# Sheet1.net
KiCad netlist of a schematic drawn in Altium Designer
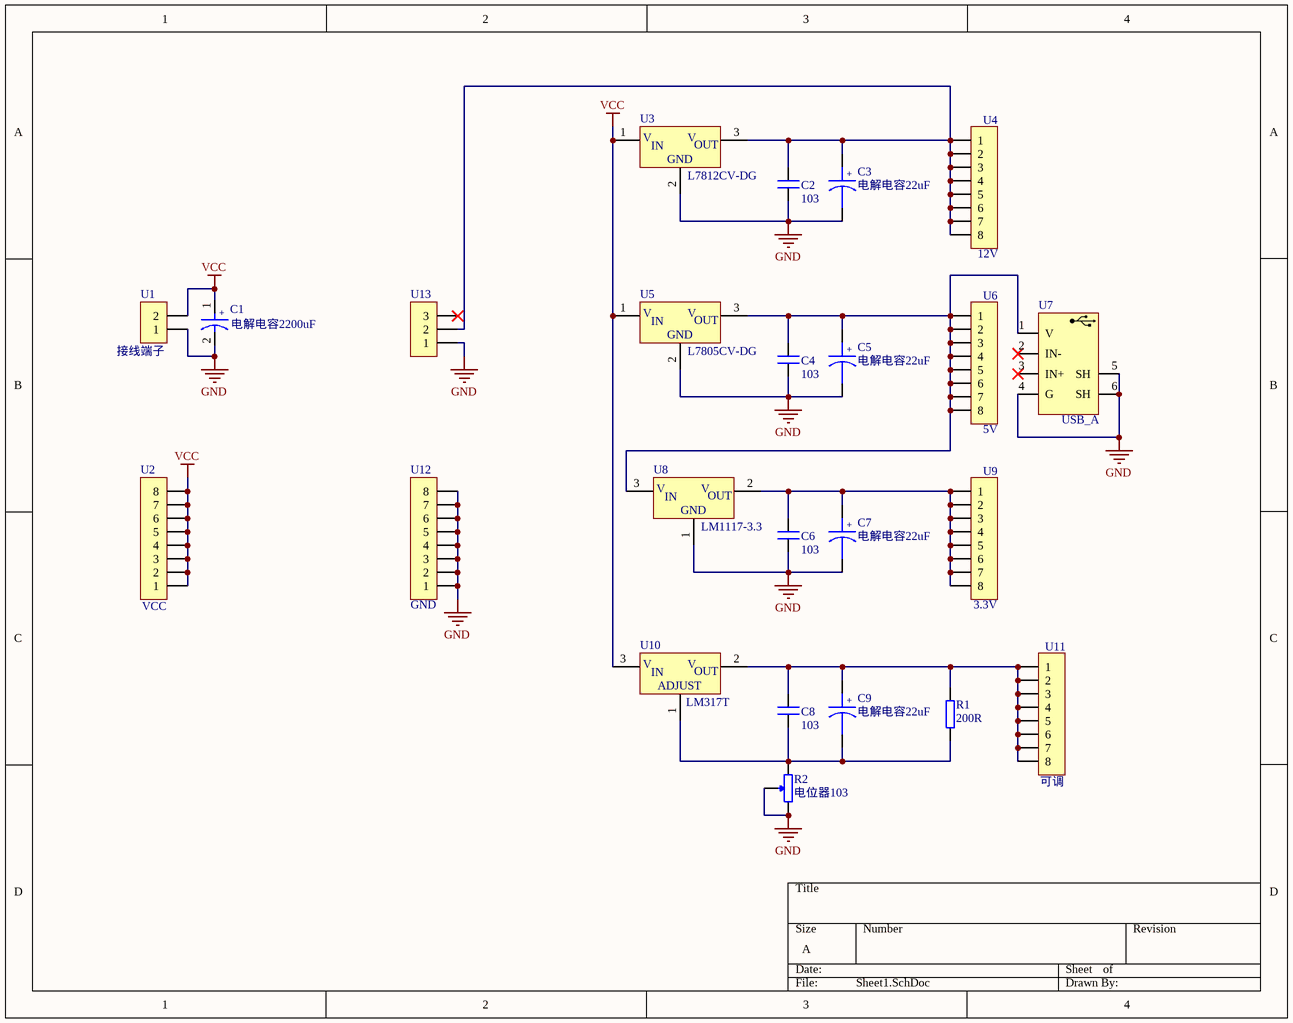
[diagram p0: Sheet1.SchDoc]

(export (version "E")
  (design (tool "Eeschema 10.0.6"))
  (components
    (comp (ref "C1")
      (value "电解电容2200uF")
      (footprint "直插电解电容13*21")
      (libsource (lib "Schlib1") (part "电解电容2200uF"))
    )
    (comp (ref "C2")
      (value "103")
      (footprint "贴片电容1206")
      (description "电容")
      (fields (field (name "版权归属") "源创客"))
      (libsource (lib "Schlib1") (part "Capacitor"))
    )
    (comp (ref "C3")
      (value "电解电容22uF")
      (footprint "直插电解电容5*11")
      (libsource (lib "Schlib1") (part "电解电容22uF"))
    )
    (comp (ref "C4")
      (value "103")
      (footprint "贴片电容1206")
      (description "电容")
      (fields (field (name "版权归属") "源创客"))
      (libsource (lib "Schlib1") (part "Capacitor"))
    )
    (comp (ref "C5")
      (value "电解电容22uF")
      (footprint "直插电解电容5*11")
      (libsource (lib "Schlib1") (part "电解电容22uF"))
    )
    (comp (ref "C6")
      (value "103")
      (footprint "贴片电容1206")
      (description "电容")
      (fields (field (name "版权归属") "源创客"))
      (libsource (lib "Schlib1") (part "Capacitor"))
    )
    (comp (ref "C7")
      (value "电解电容22uF")
      (footprint "直插电解电容5*11")
      (libsource (lib "Schlib1") (part "电解电容22uF"))
    )
    (comp (ref "C8")
      (value "103")
      (footprint "贴片电容1206")
      (description "电容")
      (fields (field (name "版权归属") "源创客"))
      (libsource (lib "Schlib1") (part "Capacitor"))
    )
    (comp (ref "C9")
      (value "电解电容22uF")
      (footprint "直插电解电容5*11")
      (libsource (lib "Schlib1") (part "电解电容22uF"))
    )
    (comp (ref "R1")
      (value "200R")
      (footprint "贴片电阻1206")
      (description "电阻")
      (fields (field (name "版权归属") "源创客"))
      (libsource (lib "Schlib1") (part "Resistor"))
    )
    (comp (ref "R2")
      (value "电位器103")
      (footprint "电位器")
      (description "103")
      (fields (field (name "版权归属") "源创客"))
      (libsource (lib "Schlib1") (part "电位器"))
    )
    (comp (ref "U1")
      (value "接线端子")
      (footprint "KF128-3.81-2P")
      (description "2P接插件")
      (fields (field (name "版权归属") "源创客"))
      (libsource (lib "Schlib1") (part "Header 2"))
    )
    (comp (ref "U2")
      (value "VCC")
      (footprint "HDR-1X8")
      (description "8P接插件")
      (fields (field (name "版权归属") "源创客"))
      (libsource (lib "") (part "Header 8_1"))
    )
    (comp (ref "U3")
      (value "L7812CV-DG")
      (footprint "TO-220")
      (description "3-Terminal Positive Voltage Regulator")
      (libsource (lib "Schlib1") (part "L7812CV-DG"))
    )
    (comp (ref "U4")
      (value "12V")
      (footprint "HDR-1X8")
      (description "8P接插件")
      (fields (field (name "版权归属") "源创客"))
      (libsource (lib "Schlib1") (part "Header 8"))
    )
    (comp (ref "U5")
      (value "L7805CV-DG")
      (footprint "TO-220")
      (description "3-Terminal Positive Voltage Regulator")
      (libsource (lib "Schlib1") (part "L7805CV-DG"))
    )
    (comp (ref "U6")
      (value "5V")
      (footprint "HDR-1X8")
      (description "8P接插件")
      (fields (field (name "版权归属") "源创客"))
      (libsource (lib "Schlib1") (part "Header 8"))
    )
    (comp (ref "U7") (value "USB_A") (footprint "USB-A直插") (libsource (lib "Schlib1") (part "USB_A")))
    (comp (ref "U8")
      (value "LM1117-3.3")
      (footprint "TO-220")
      (description "3-Terminal Positive Voltage Regulator")
      (libsource (lib "Schlib1") (part "LM1117-3.3"))
    )
    (comp (ref "U9")
      (value "3.3V")
      (footprint "HDR-1X8")
      (description "8P接插件")
      (fields (field (name "版权归属") "源创客"))
      (libsource (lib "Schlib1") (part "Header 8"))
    )
    (comp (ref "U10")
      (value "LM317T")
      (footprint "TO-220")
      (description "3-Terminal Positive Voltage Regulator")
      (libsource (lib "Schlib1") (part "LM317T"))
    )
    (comp (ref "U11")
      (value "可调")
      (footprint "HDR-1X8")
      (description "8P接插件")
      (fields (field (name "版权归属") "源创客"))
      (libsource (lib "Schlib1") (part "Header 8"))
    )
    (comp (ref "U12")
      (value "GND")
      (footprint "HDR-1X8")
      (description "8P接插件")
      (fields (field (name "版权归属") "源创客"))
      (libsource (lib "") (part "Header 8_1"))
    )
    (comp (ref "U13")
      (value "接插件")
      (footprint "KF2510")
      (description "3P接插件")
      (fields (field (name "版权归属") "源创客"))
      (libsource (lib "Schlib1") (part "Header 3"))
    )
  )
  (nets
    (net (code "1") (name "GND") (class "Default")
      (node (ref "C1") (pin "2") (pinfunction "2_2") (pintype "passive"))
      (node (ref "C2") (pin "1") (pinfunction "1_1") (pintype "passive"))
      (node (ref "C3") (pin "2") (pinfunction "2_2") (pintype "passive"))
      (node (ref "C4") (pin "1") (pinfunction "1_1") (pintype "passive"))
      (node (ref "C5") (pin "2") (pinfunction "2_2") (pintype "passive"))
      (node (ref "C6") (pin "1") (pinfunction "1_1") (pintype "passive"))
      (node (ref "C7") (pin "2") (pinfunction "2_2") (pintype "passive"))
      (node (ref "R2") (pin "1") (pinfunction "1_1") (pintype "passive"))
      (node (ref "R2") (pin "2") (pinfunction "2_2") (pintype "passive"))
      (node (ref "U1") (pin "1") (pinfunction "1_1") (pintype "passive"))
      (node (ref "U12") (pin "1") (pinfunction "1_1") (pintype "passive"))
      (node (ref "U12") (pin "2") (pinfunction "2_2") (pintype "passive"))
      (node (ref "U12") (pin "3") (pinfunction "3_3") (pintype "passive"))
      (node (ref "U12") (pin "4") (pinfunction "4_4") (pintype "passive"))
      (node (ref "U12") (pin "5") (pinfunction "5_5") (pintype "passive"))
      (node (ref "U12") (pin "6") (pinfunction "6_6") (pintype "passive"))
      (node (ref "U12") (pin "7") (pinfunction "7_7") (pintype "passive"))
      (node (ref "U12") (pin "8") (pinfunction "8_8") (pintype "passive"))
      (node (ref "U13") (pin "1") (pinfunction "1_1") (pintype "passive"))
      (node (ref "U3") (pin "2") (pinfunction "GND_2") (pintype "passive"))
      (node (ref "U5") (pin "2") (pinfunction "GND_2") (pintype "passive"))
      (node (ref "U7") (pin "4") (pinfunction "G_4") (pintype "passive"))
      (node (ref "U7") (pin "5") (pinfunction "SH_5") (pintype "passive"))
      (node (ref "U7") (pin "6") (pinfunction "SH_6") (pintype "passive"))
      (node (ref "U8") (pin "1") (pinfunction "GND_1") (pintype "passive"))
    )
    (net (code "2") (name "Net-(U3-VOUT)") (class "Default")
      (node (ref "C2") (pin "2") (pinfunction "2_2") (pintype "passive"))
      (node (ref "C3") (pin "1") (pinfunction "1_1") (pintype "passive"))
      (node (ref "U13") (pin "2") (pinfunction "2_2") (pintype "passive"))
      (node (ref "U3") (pin "3") (pinfunction "VOUT_3") (pintype "passive"))
      (node (ref "U4") (pin "1") (pinfunction "1_1") (pintype "passive"))
      (node (ref "U4") (pin "2") (pinfunction "2_2") (pintype "passive"))
      (node (ref "U4") (pin "3") (pinfunction "3_3") (pintype "passive"))
      (node (ref "U4") (pin "4") (pinfunction "4_4") (pintype "passive"))
      (node (ref "U4") (pin "5") (pinfunction "5_5") (pintype "passive"))
      (node (ref "U4") (pin "6") (pinfunction "6_6") (pintype "passive"))
      (node (ref "U4") (pin "7") (pinfunction "7_7") (pintype "passive"))
      (node (ref "U4") (pin "8") (pinfunction "8_8") (pintype "passive"))
    )
    (net (code "3") (name "Net-(U5-VOUT)") (class "Default")
      (node (ref "C4") (pin "2") (pinfunction "2_2") (pintype "passive"))
      (node (ref "C5") (pin "1") (pinfunction "1_1") (pintype "passive"))
      (node (ref "U5") (pin "3") (pinfunction "VOUT_3") (pintype "passive"))
      (node (ref "U6") (pin "1") (pinfunction "1_1") (pintype "passive"))
      (node (ref "U6") (pin "2") (pinfunction "2_2") (pintype "passive"))
      (node (ref "U6") (pin "3") (pinfunction "3_3") (pintype "passive"))
      (node (ref "U6") (pin "4") (pinfunction "4_4") (pintype "passive"))
      (node (ref "U6") (pin "5") (pinfunction "5_5") (pintype "passive"))
      (node (ref "U6") (pin "6") (pinfunction "6_6") (pintype "passive"))
      (node (ref "U6") (pin "7") (pinfunction "7_7") (pintype "passive"))
      (node (ref "U6") (pin "8") (pinfunction "8_8") (pintype "passive"))
      (node (ref "U7") (pin "1") (pinfunction "V_1") (pintype "passive"))
      (node (ref "U8") (pin "3") (pinfunction "VIN_3") (pintype "passive"))
    )
    (net (code "4") (name "Net-(U8-VOUT)") (class "Default")
      (node (ref "C6") (pin "2") (pinfunction "2_2") (pintype "passive"))
      (node (ref "C7") (pin "1") (pinfunction "1_1") (pintype "passive"))
      (node (ref "U8") (pin "2") (pinfunction "VOUT_2") (pintype "passive"))
      (node (ref "U9") (pin "1") (pinfunction "1_1") (pintype "passive"))
      (node (ref "U9") (pin "2") (pinfunction "2_2") (pintype "passive"))
      (node (ref "U9") (pin "3") (pinfunction "3_3") (pintype "passive"))
      (node (ref "U9") (pin "4") (pinfunction "4_4") (pintype "passive"))
      (node (ref "U9") (pin "5") (pinfunction "5_5") (pintype "passive"))
      (node (ref "U9") (pin "6") (pinfunction "6_6") (pintype "passive"))
      (node (ref "U9") (pin "7") (pinfunction "7_7") (pintype "passive"))
      (node (ref "U9") (pin "8") (pinfunction "8_8") (pintype "passive"))
    )
    (net (code "5") (name "Net-(U10-GND)") (class "Default")
      (node (ref "C8") (pin "1") (pinfunction "1_1") (pintype "passive"))
      (node (ref "C9") (pin "2") (pinfunction "2_2") (pintype "passive"))
      (node (ref "R1") (pin "1") (pinfunction "1_1") (pintype "passive"))
      (node (ref "R2") (pin "3") (pinfunction "3_3") (pintype "passive"))
      (node (ref "U10") (pin "1") (pinfunction "GND_1") (pintype "passive"))
    )
    (net (code "6") (name "Net-(U10-VOUT)") (class "Default")
      (node (ref "C8") (pin "2") (pinfunction "2_2") (pintype "passive"))
      (node (ref "C9") (pin "1") (pinfunction "1_1") (pintype "passive"))
      (node (ref "R1") (pin "2") (pinfunction "2_2") (pintype "passive"))
      (node (ref "U10") (pin "2") (pinfunction "VOUT_2") (pintype "passive"))
      (node (ref "U11") (pin "1") (pinfunction "1_1") (pintype "passive"))
      (node (ref "U11") (pin "2") (pinfunction "2_2") (pintype "passive"))
      (node (ref "U11") (pin "3") (pinfunction "3_3") (pintype "passive"))
      (node (ref "U11") (pin "4") (pinfunction "4_4") (pintype "passive"))
      (node (ref "U11") (pin "5") (pinfunction "5_5") (pintype "passive"))
      (node (ref "U11") (pin "6") (pinfunction "6_6") (pintype "passive"))
      (node (ref "U11") (pin "7") (pinfunction "7_7") (pintype "passive"))
      (node (ref "U11") (pin "8") (pinfunction "8_8") (pintype "passive"))
    )
    (net (code "7") (name "VCC") (class "Default")
      (node (ref "C1") (pin "1") (pinfunction "1_1") (pintype "passive"))
      (node (ref "U1") (pin "2") (pinfunction "2_2") (pintype "passive"))
      (node (ref "U10") (pin "3") (pinfunction "VIN_3") (pintype "passive"))
      (node (ref "U2") (pin "1") (pinfunction "1_1") (pintype "passive"))
      (node (ref "U2") (pin "2") (pinfunction "2_2") (pintype "passive"))
      (node (ref "U2") (pin "3") (pinfunction "3_3") (pintype "passive"))
      (node (ref "U2") (pin "4") (pinfunction "4_4") (pintype "passive"))
      (node (ref "U2") (pin "5") (pinfunction "5_5") (pintype "passive"))
      (node (ref "U2") (pin "6") (pinfunction "6_6") (pintype "passive"))
      (node (ref "U2") (pin "7") (pinfunction "7_7") (pintype "passive"))
      (node (ref "U2") (pin "8") (pinfunction "8_8") (pintype "passive"))
      (node (ref "U3") (pin "1") (pinfunction "VIN_1") (pintype "passive"))
      (node (ref "U5") (pin "1") (pinfunction "VIN_1") (pintype "passive"))
    )
    (net (code "8") (name "unconnected-(U7-IN+-Pad3)") (class "Default")
      (node (ref "U7") (pin "3") (pinfunction "IN+_3") (pintype "passive+no_connect"))
    )
    (net (code "9") (name "unconnected-(U7-IN--Pad2)") (class "Default")
      (node (ref "U7") (pin "2") (pinfunction "IN-_2") (pintype "passive+no_connect"))
    )
    (net (code "10") (name "unconnected-(U13-Pad3)") (class "Default")
      (node (ref "U13") (pin "3") (pinfunction "3_3") (pintype "passive+no_connect"))
    )
  )
)
